# 19_WIFI_BLE.net
KiCad netlist of a schematic drawn in Altium Designer
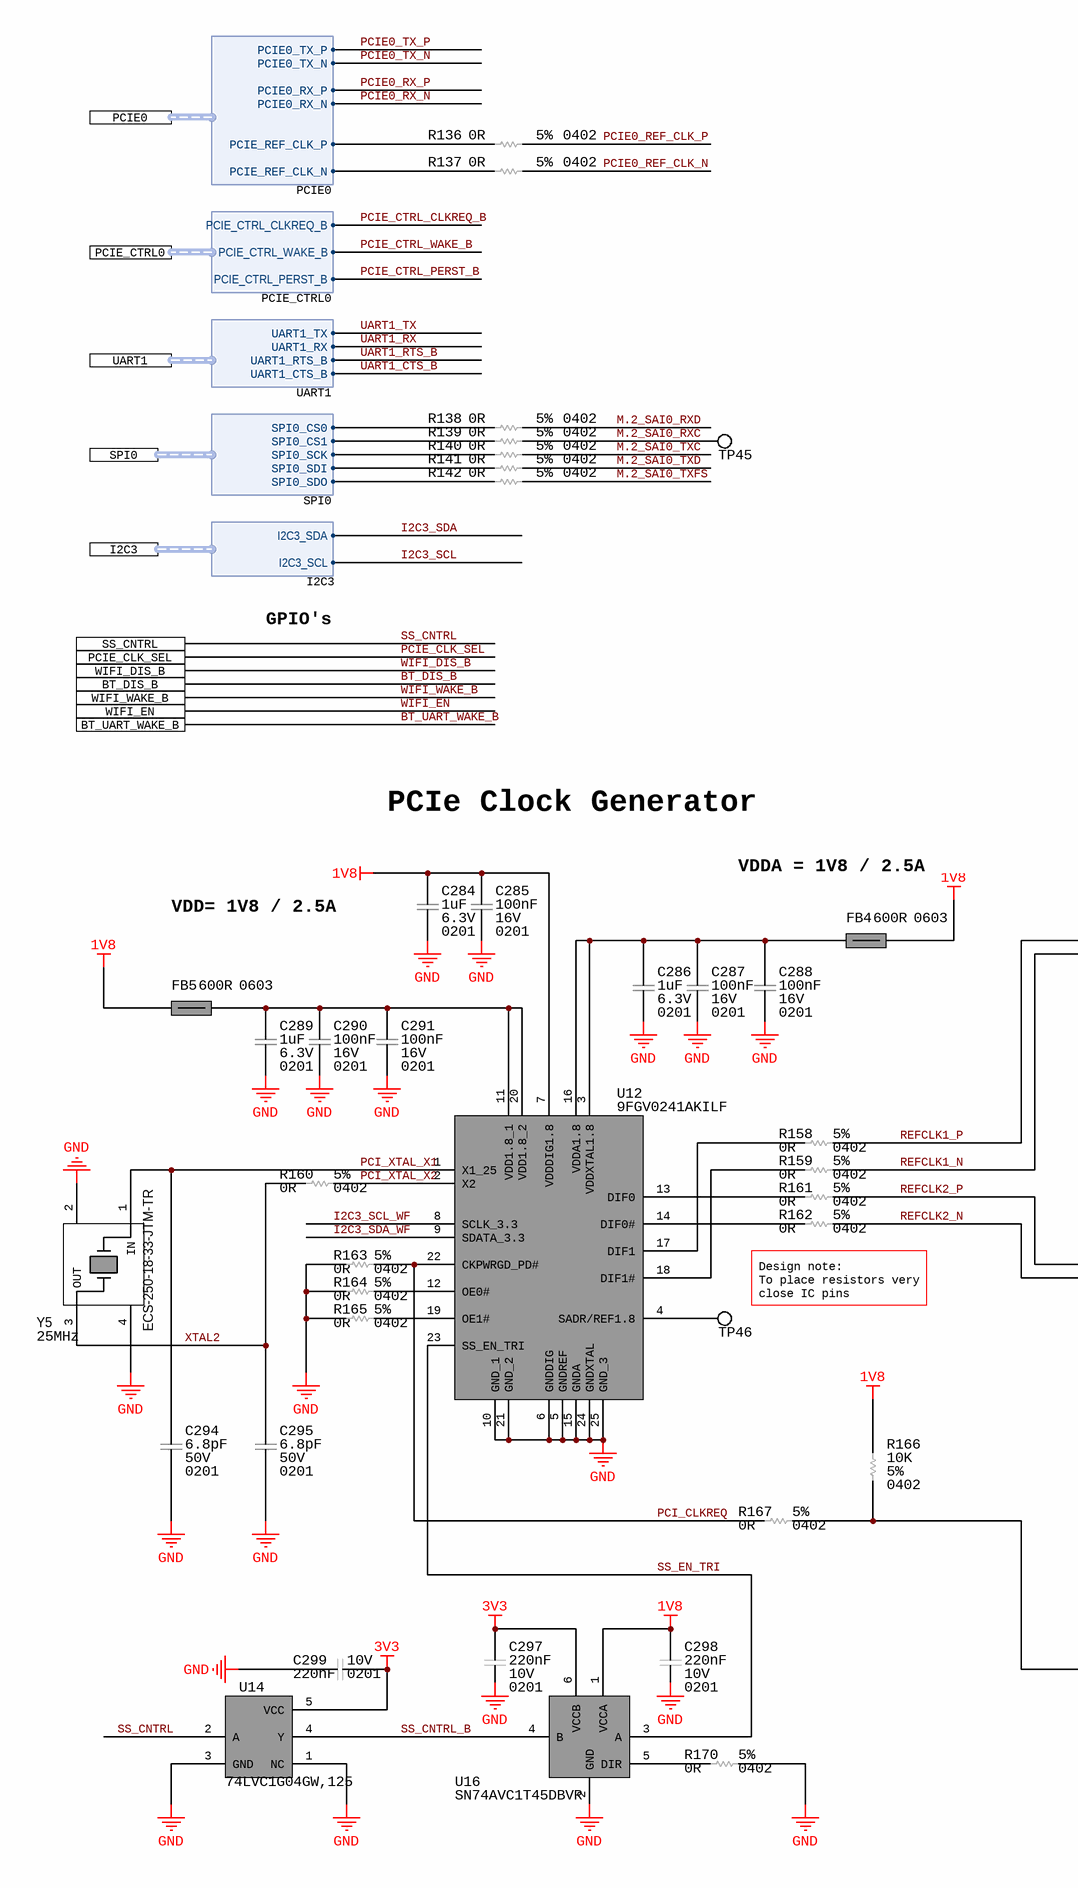
[diagram p0: 19_WIFI_BLE.SchDoc, left]
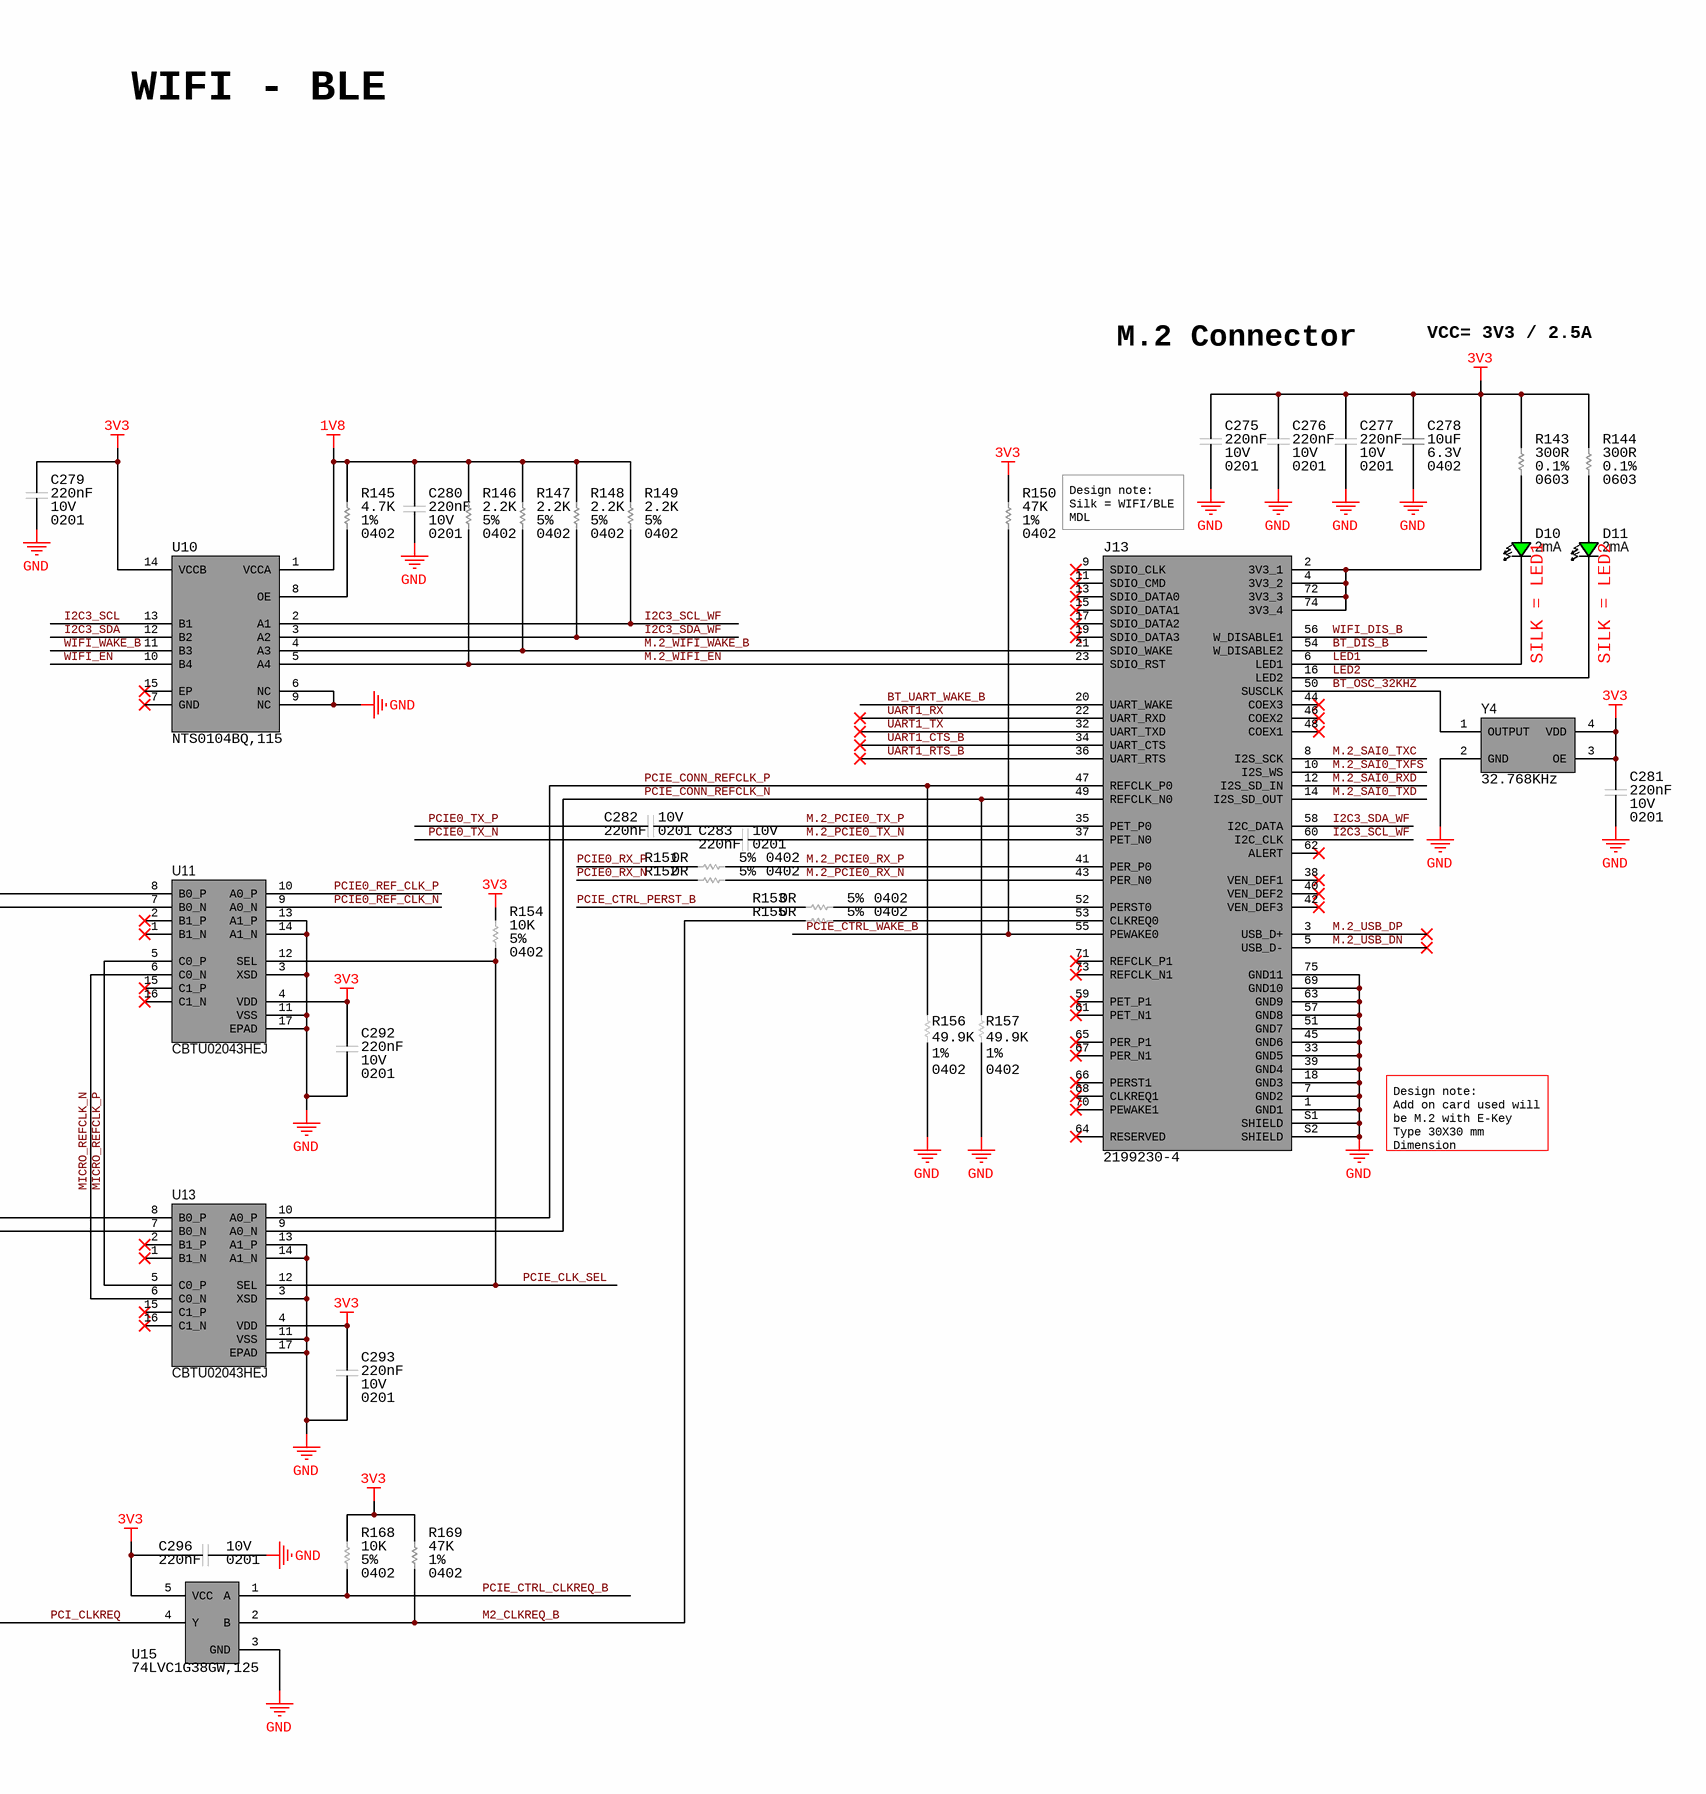
[diagram p1: 19_WIFI_BLE.SchDoc, right]

(export (version "E")
  (design (tool "Eeschema 10.0.6"))
  (components
    (comp (ref "C275")
      (value "LMK063BJ224MP-F")
      (footprint "CAP_0201_CAPC0603X03N")
      (description "Multilayer Ceramic Capacitors (High dielectric type), 10V, 0.22 uF, ± 20 %, 0201, X5R, RoHS")
      (fields
        (field (name "MANUFACTURER") "Taiyo Yuden")
        (field (name "TOLERANCE") "20%")
        (field (name "VOLTAGE RATING (DC)") "10V")
        (field (name "CAPACITANCE") "220nF")
        (field (name "CASE/PACKAGE") "0201")
      )
      (libsource (lib "Electronic Devices_LIB") (part "CAP_0.22UF_10V_X5R_0201"))
    )
    (comp (ref "C276")
      (value "LMK063BJ224MP-F")
      (footprint "CAP_0201_CAPC0603X03N")
      (description "Multilayer Ceramic Capacitors (High dielectric type), 10V, 0.22 uF, ± 20 %, 0201, X5R, RoHS")
      (fields
        (field (name "MANUFACTURER") "Taiyo Yuden")
        (field (name "TOLERANCE") "20%")
        (field (name "VOLTAGE RATING (DC)") "10V")
        (field (name "CAPACITANCE") "220nF")
        (field (name "CASE/PACKAGE") "0201")
      )
      (libsource (lib "Electronic Devices_LIB") (part "CAP_0.22UF_10V_X5R_0201"))
    )
    (comp (ref "C277")
      (value "LMK063BJ224MP-F")
      (footprint "CAP_0201_CAPC0603X03N")
      (description "Multilayer Ceramic Capacitors (High dielectric type), 10V, 0.22 uF, ± 20 %, 0201, X5R, RoHS")
      (fields
        (field (name "MANUFACTURER") "Taiyo Yuden")
        (field (name "TOLERANCE") "20%")
        (field (name "VOLTAGE RATING (DC)") "10V")
        (field (name "CAPACITANCE") "220nF")
        (field (name "CASE/PACKAGE") "0201")
      )
      (libsource (lib "Electronic Devices_LIB") (part "CAP_0.22UF_10V_X5R_0201"))
    )
    (comp (ref "C278")
      (value "CL05A106MQ5NUNC")
      (footprint "CAP_0402_CAPC1005X05N")
      (description "Cap Ceramic 10uF 6.3V X5R 20% SMD 0402 85C T/R")
      (fields
        (field (name "MANUFACTURER") "Samsung")
        (field (name "TOLERANCE") "20%")
        (field (name "CASE/PACKAGE") "0402")
        (field (name "CAPACITANCE") "10uF")
        (field (name "VOLTAGE RATING") "6.3V")
      )
      (libsource (lib "Electronic Devices_LIB") (part "CAP_10UF_6.3V_X5R_0402"))
    )
    (comp (ref "C279")
      (value "LMK063BJ224MP-F")
      (footprint "CAP_0201_CAPC0603X03N")
      (description "Multilayer Ceramic Capacitors (High dielectric type), 10V, 0.22 uF, ± 20 %, 0201, X5R, RoHS")
      (fields
        (field (name "MANUFACTURER") "Taiyo Yuden")
        (field (name "TOLERANCE") "20%")
        (field (name "VOLTAGE RATING (DC)") "10V")
        (field (name "CAPACITANCE") "220nF")
        (field (name "CASE/PACKAGE") "0201")
      )
      (libsource (lib "Electronic Devices_LIB") (part "CAP_0.22UF_10V_X5R_0201"))
    )
    (comp (ref "C280")
      (value "LMK063BJ224MP-F")
      (footprint "CAP_0201_CAPC0603X03N")
      (description "Multilayer Ceramic Capacitors (High dielectric type), 10V, 0.22 uF, ± 20 %, 0201, X5R, RoHS")
      (fields
        (field (name "MANUFACTURER") "Taiyo Yuden")
        (field (name "TOLERANCE") "20%")
        (field (name "VOLTAGE RATING (DC)") "10V")
        (field (name "CAPACITANCE") "220nF")
        (field (name "CASE/PACKAGE") "0201")
      )
      (libsource (lib "Electronic Devices_LIB") (part "CAP_0.22UF_10V_X5R_0201"))
    )
    (comp (ref "C281")
      (value "LMK063BJ224MP-F")
      (footprint "CAP_0201_CAPC0603X03N")
      (description "Multilayer Ceramic Capacitors (High dielectric type), 10V, 0.22 uF, ± 20 %, 0201, X5R, RoHS")
      (fields
        (field (name "MANUFACTURER") "Taiyo Yuden")
        (field (name "TOLERANCE") "20%")
        (field (name "VOLTAGE RATING (DC)") "10V")
        (field (name "CAPACITANCE") "220nF")
        (field (name "CASE/PACKAGE") "0201")
      )
      (libsource (lib "Electronic Devices_LIB") (part "CAP_0.22UF_10V_X5R_0201"))
    )
    (comp (ref "C282")
      (value "LMK063BJ224MP-F")
      (footprint "CAP_0201_CAPC0603X03N")
      (description "Multilayer Ceramic Capacitors (High dielectric type), 10V, 0.22 uF, ± 20 %, 0201, X5R, RoHS")
      (fields
        (field (name "MANUFACTURER") "Taiyo Yuden")
        (field (name "TOLERANCE") "20%")
        (field (name "VOLTAGE RATING (DC)") "10V")
        (field (name "CAPACITANCE") "220nF")
        (field (name "CASE/PACKAGE") "0201")
      )
      (libsource (lib "Electronic Devices_LIB") (part "CAP_0.22UF_10V_X5R_0201"))
    )
    (comp (ref "C283")
      (value "LMK063BJ224MP-F")
      (footprint "CAP_0201_CAPC0603X03N")
      (description "Multilayer Ceramic Capacitors (High dielectric type), 10V, 0.22 uF, ± 20 %, 0201, X5R, RoHS")
      (fields
        (field (name "MANUFACTURER") "Taiyo Yuden")
        (field (name "TOLERANCE") "20%")
        (field (name "VOLTAGE RATING (DC)") "10V")
        (field (name "CAPACITANCE") "220nF")
        (field (name "CASE/PACKAGE") "0201")
      )
      (libsource (lib "Electronic Devices_LIB") (part "CAP_0.22UF_10V_X5R_0201"))
    )
    (comp (ref "C284")
      (value "02016D105MAT2A")
      (footprint "CAP_0201_CAPC0603X03N")
      (description "0201 1 uF 6.3 V ±20 % Tolerance X5R Surface Mount Multilayer Ceramic Capacitor")
      (fields
        (field (name "MANUFACTURER") "Kyocera AVX")
        (field (name "TOLERANCE") "20%")
        (field (name "VOLTAGE RATING (DC)") "6.3V")
        (field (name "CAPACITANCE") "1uF")
        (field (name "CASE/PACKAGE") "0201")
      )
      (libsource (lib "Electronic Devices_LIB") (part "CAP_1UF_6.3V_X5R_0201"))
    )
    (comp (ref "C285")
      (value "GRM033C71C104KE14D")
      (footprint "CAP_0201_CAPC0603X03N")
      (description "Multilayer Ceramic Capacitor, 0.1 uF, 16 V, ± 10%, X7S, 0201 [0603 Metric]")
      (fields
        (field (name "MANUFACTURER") "Murata")
        (field (name "TOLERANCE") "10%")
        (field (name "VOLTAGE RATING") "16V")
        (field (name "CAPACITANCE") "100nF")
        (field (name "CASE/PACKAGE") "0201")
      )
      (libsource (lib "Electronic Devices_LIB") (part "CAP_100nF_16V_X7S_0201"))
    )
    (comp (ref "C286")
      (value "02016D105MAT2A")
      (footprint "CAP_0201_CAPC0603X03N")
      (description "0201 1 uF 6.3 V ±20 % Tolerance X5R Surface Mount Multilayer Ceramic Capacitor")
      (fields
        (field (name "MANUFACTURER") "Kyocera AVX")
        (field (name "TOLERANCE") "20%")
        (field (name "VOLTAGE RATING (DC)") "6.3V")
        (field (name "CAPACITANCE") "1uF")
        (field (name "CASE/PACKAGE") "0201")
      )
      (libsource (lib "Electronic Devices_LIB") (part "CAP_1UF_6.3V_X5R_0201"))
    )
    (comp (ref "C287")
      (value "GRM033C71C104KE14D")
      (footprint "CAP_0201_CAPC0603X03N")
      (description "Multilayer Ceramic Capacitor, 0.1 uF, 16 V, ± 10%, X7S, 0201 [0603 Metric]")
      (fields
        (field (name "MANUFACTURER") "Murata")
        (field (name "TOLERANCE") "10%")
        (field (name "VOLTAGE RATING") "16V")
        (field (name "CAPACITANCE") "100nF")
        (field (name "CASE/PACKAGE") "0201")
      )
      (libsource (lib "Electronic Devices_LIB") (part "CAP_100nF_16V_X7S_0201"))
    )
    (comp (ref "C288")
      (value "GRM033C71C104KE14D")
      (footprint "CAP_0201_CAPC0603X03N")
      (description "Multilayer Ceramic Capacitor, 0.1 uF, 16 V, ± 10%, X7S, 0201 [0603 Metric]")
      (fields
        (field (name "MANUFACTURER") "Murata")
        (field (name "TOLERANCE") "10%")
        (field (name "VOLTAGE RATING") "16V")
        (field (name "CAPACITANCE") "100nF")
        (field (name "CASE/PACKAGE") "0201")
      )
      (libsource (lib "Electronic Devices_LIB") (part "CAP_100nF_16V_X7S_0201"))
    )
    (comp (ref "C289")
      (value "02016D105MAT2A")
      (footprint "CAP_0201_CAPC0603X03N")
      (description "0201 1 uF 6.3 V ±20 % Tolerance X5R Surface Mount Multilayer Ceramic Capacitor")
      (fields
        (field (name "MANUFACTURER") "Kyocera AVX")
        (field (name "TOLERANCE") "20%")
        (field (name "VOLTAGE RATING (DC)") "6.3V")
        (field (name "CAPACITANCE") "1uF")
        (field (name "CASE/PACKAGE") "0201")
      )
      (libsource (lib "Electronic Devices_LIB") (part "CAP_1UF_6.3V_X5R_0201"))
    )
    (comp (ref "C290")
      (value "GRM033C71C104KE14D")
      (footprint "CAP_0201_CAPC0603X03N")
      (description "Multilayer Ceramic Capacitor, 0.1 uF, 16 V, ± 10%, X7S, 0201 [0603 Metric]")
      (fields
        (field (name "MANUFACTURER") "Murata")
        (field (name "TOLERANCE") "10%")
        (field (name "VOLTAGE RATING") "16V")
        (field (name "CAPACITANCE") "100nF")
        (field (name "CASE/PACKAGE") "0201")
      )
      (libsource (lib "Electronic Devices_LIB") (part "CAP_100nF_16V_X7S_0201"))
    )
    (comp (ref "C291")
      (value "GRM033C71C104KE14D")
      (footprint "CAP_0201_CAPC0603X03N")
      (description "Multilayer Ceramic Capacitor, 0.1 uF, 16 V, ± 10%, X7S, 0201 [0603 Metric]")
      (fields
        (field (name "MANUFACTURER") "Murata")
        (field (name "TOLERANCE") "10%")
        (field (name "VOLTAGE RATING") "16V")
        (field (name "CAPACITANCE") "100nF")
        (field (name "CASE/PACKAGE") "0201")
      )
      (libsource (lib "Electronic Devices_LIB") (part "CAP_100nF_16V_X7S_0201"))
    )
    (comp (ref "C292")
      (value "LMK063BJ224MP-F")
      (footprint "CAP_0201_CAPC0603X03N")
      (description "Multilayer Ceramic Capacitors (High dielectric type), 10V, 0.22 uF, ± 20 %, 0201, X5R, RoHS")
      (fields
        (field (name "MANUFACTURER") "Taiyo Yuden")
        (field (name "TOLERANCE") "20%")
        (field (name "VOLTAGE RATING (DC)") "10V")
        (field (name "CAPACITANCE") "220nF")
        (field (name "CASE/PACKAGE") "0201")
      )
      (libsource (lib "Electronic Devices_LIB") (part "CAP_0.22UF_10V_X5R_0201"))
    )
    (comp (ref "C293")
      (value "LMK063BJ224MP-F")
      (footprint "CAP_0201_CAPC0603X03N")
      (description "Multilayer Ceramic Capacitors (High dielectric type), 10V, 0.22 uF, ± 20 %, 0201, X5R, RoHS")
      (fields
        (field (name "MANUFACTURER") "Taiyo Yuden")
        (field (name "TOLERANCE") "20%")
        (field (name "VOLTAGE RATING (DC)") "10V")
        (field (name "CAPACITANCE") "220nF")
        (field (name "CASE/PACKAGE") "0201")
      )
      (libsource (lib "Electronic Devices_LIB") (part "CAP_0.22UF_10V_X5R_0201"))
    )
    (comp (ref "C294")
      (value "GRM0335C1H6R8BA01D")
      (footprint "CAP_0201_CAPC0603X03N")
      (description "Cap Ceramic 6.8pF 50V C0G 0.1pF Pad SMD 0201 125C T/R")
      (fields
        (field (name "MANUFACTURER") "Murata")
        (field (name "CAPACITANCE") "6.8pF")
        (field (name "VOLTAGE RATING") "50V")
        (field (name "CASE/PACKAGE") "0201")
      )
      (libsource (lib "Electronic Devices_LIB") (part "CAP_6.8pF_50V_NP0_0201"))
    )
    (comp (ref "C295")
      (value "GRM0335C1H6R8BA01D")
      (footprint "CAP_0201_CAPC0603X03N")
      (description "Cap Ceramic 6.8pF 50V C0G 0.1pF Pad SMD 0201 125C T/R")
      (fields
        (field (name "MANUFACTURER") "Murata")
        (field (name "CAPACITANCE") "6.8pF")
        (field (name "VOLTAGE RATING") "50V")
        (field (name "CASE/PACKAGE") "0201")
      )
      (libsource (lib "Electronic Devices_LIB") (part "CAP_6.8pF_50V_NP0_0201"))
    )
    (comp (ref "C296")
      (value "LMK063BJ224MP-F")
      (footprint "CAP_0201_CAPC0603X03N")
      (description "Multilayer Ceramic Capacitors (High dielectric type), 10V, 0.22 uF, ± 20 %, 0201, X5R, RoHS")
      (fields
        (field (name "MANUFACTURER") "Taiyo Yuden")
        (field (name "TOLERANCE") "20%")
        (field (name "VOLTAGE RATING (DC)") "10V")
        (field (name "CAPACITANCE") "220nF")
        (field (name "CASE/PACKAGE") "0201")
      )
      (libsource (lib "Electronic Devices_LIB") (part "CAP_0.22UF_10V_X5R_0201"))
    )
    (comp (ref "C297")
      (value "LMK063BJ224MP-F")
      (footprint "CAP_0201_CAPC0603X03N")
      (description "Multilayer Ceramic Capacitors (High dielectric type), 10V, 0.22 uF, ± 20 %, 0201, X5R, RoHS")
      (fields
        (field (name "MANUFACTURER") "Taiyo Yuden")
        (field (name "TOLERANCE") "20%")
        (field (name "VOLTAGE RATING (DC)") "10V")
        (field (name "CAPACITANCE") "220nF")
        (field (name "CASE/PACKAGE") "0201")
      )
      (libsource (lib "Electronic Devices_LIB") (part "CAP_0.22UF_10V_X5R_0201"))
    )
    (comp (ref "C298")
      (value "LMK063BJ224MP-F")
      (footprint "CAP_0201_CAPC0603X03N")
      (description "Multilayer Ceramic Capacitors (High dielectric type), 10V, 0.22 uF, ± 20 %, 0201, X5R, RoHS")
      (fields
        (field (name "MANUFACTURER") "Taiyo Yuden")
        (field (name "TOLERANCE") "20%")
        (field (name "VOLTAGE RATING (DC)") "10V")
        (field (name "CAPACITANCE") "220nF")
        (field (name "CASE/PACKAGE") "0201")
      )
      (libsource (lib "Electronic Devices_LIB") (part "CAP_0.22UF_10V_X5R_0201"))
    )
    (comp (ref "C299")
      (value "LMK063BJ224MP-F")
      (footprint "CAP_0201_CAPC0603X03N")
      (description "Multilayer Ceramic Capacitors (High dielectric type), 10V, 0.22 uF, ± 20 %, 0201, X5R, RoHS")
      (fields
        (field (name "MANUFACTURER") "Taiyo Yuden")
        (field (name "TOLERANCE") "20%")
        (field (name "VOLTAGE RATING (DC)") "10V")
        (field (name "CAPACITANCE") "220nF")
        (field (name "CASE/PACKAGE") "0201")
      )
      (libsource (lib "Electronic Devices_LIB") (part "CAP_0.22UF_10V_X5R_0201"))
    )
    (comp (ref "D10")
      (value "APDA3020LZGCK")
      (footprint "LED_GREEN_APDA3020LZGCK")
      (description "LED GREEN CLEAR 2SMD R/A  1500mcd")
      (fields (field (name "MANUFACTURER") "Kingbright") (field (name "TEST CURRENT") "2mA"))
      (libsource (lib "Electronic Devices_LIB") (part "LED_DIO_GREEN_2mA_APDA3020LZGCK"))
    )
    (comp (ref "D11")
      (value "APDA3020LZGCK")
      (footprint "LED_GREEN_APDA3020LZGCK")
      (description "LED GREEN CLEAR 2SMD R/A  1500mcd")
      (fields (field (name "MANUFACTURER") "Kingbright") (field (name "TEST CURRENT") "2mA"))
      (libsource (lib "Electronic Devices_LIB") (part "LED_DIO_GREEN_2mA_APDA3020LZGCK"))
    )
    (comp (ref "FB4")
      (value "742792653")
      (footprint "IND_0603_INDC1608X08N")
      (description "Chip NTC Thermistors (Sensor), Resistance (at 25°C)=10kΩ, Resistance Tolerance (at 25°C)=±1%")
      (fields
        (field (name "MANUFACTURER") "Wurth Electronics")
        (field (name "TOLERANCE") "25%")
        (field (name "IMPEDANCE") "600R")
        (field (name "CASE CODE (IMPERIAL)") "0603")
      )
      (libsource (lib "Electronic Devices_LIB") (part "IND_FERRITE_BEADS_600R_300mA_0603_742792653"))
    )
    (comp (ref "FB5")
      (value "742792653")
      (footprint "IND_0603_INDC1608X08N")
      (description "Chip NTC Thermistors (Sensor), Resistance (at 25°C)=10kΩ, Resistance Tolerance (at 25°C)=±1%")
      (fields
        (field (name "MANUFACTURER") "Wurth Electronics")
        (field (name "TOLERANCE") "25%")
        (field (name "IMPEDANCE") "600R")
        (field (name "CASE CODE (IMPERIAL)") "0603")
      )
      (libsource (lib "Electronic Devices_LIB") (part "IND_FERRITE_BEADS_600R_300mA_0603_742792653"))
    )
    (comp (ref "J13")
      (value "2199230-4")
      (footprint "TE_21992304")
      (description "CONNECTOR, BACKPLANE, HOUSING, RCPT, 67POS, 2ROW; Connector Type: Card Edge; Seri")
      (fields (field (name "MANUFACTURER") "TE Connectivity"))
      (libsource (lib "Electronic Devices_LIB") (part "CONN_M.2_FEMALE_2199230-4"))
    )
    (comp (ref "R136")
      (value "ERJ-2GE0R00X")
      (footprint "RES_0402_RESC1005X04N")
      (description "SMD Chip Resistor, Jumper, 0 ohm, 100 mW, 0402 [1005 Metric], Thick Film, General Purpose")
      (fields
        (field (name "MANUFACTURER") "Panasonic")
        (field (name "CASE CODE (IMPERIAL)") "0402")
        (field (name "TOLERANCE") "5%")
        (field (name "RESISTANCE") "0R")
      )
      (libsource (lib "Electronic Devices_LIB") (part "RES_0R_5%_100mW_0402"))
    )
    (comp (ref "R137")
      (value "ERJ-2GE0R00X")
      (footprint "RES_0402_RESC1005X04N")
      (description "SMD Chip Resistor, Jumper, 0 ohm, 100 mW, 0402 [1005 Metric], Thick Film, General Purpose")
      (fields
        (field (name "MANUFACTURER") "Panasonic")
        (field (name "CASE CODE (IMPERIAL)") "0402")
        (field (name "TOLERANCE") "5%")
        (field (name "RESISTANCE") "0R")
      )
      (libsource (lib "Electronic Devices_LIB") (part "RES_0R_5%_100mW_0402"))
    )
    (comp (ref "R138")
      (value "ERJ-2GE0R00X")
      (footprint "RES_0402_RESC1005X04N")
      (description "SMD Chip Resistor, Jumper, 0 ohm, 100 mW, 0402 [1005 Metric], Thick Film, General Purpose")
      (fields
        (field (name "MANUFACTURER") "Panasonic")
        (field (name "CASE CODE (IMPERIAL)") "0402")
        (field (name "TOLERANCE") "5%")
        (field (name "RESISTANCE") "0R")
      )
      (libsource (lib "Electronic Devices_LIB") (part "RES_0R_5%_100mW_0402"))
    )
    (comp (ref "R139")
      (value "ERJ-2GE0R00X")
      (footprint "RES_0402_RESC1005X04N")
      (description "SMD Chip Resistor, Jumper, 0 ohm, 100 mW, 0402 [1005 Metric], Thick Film, General Purpose")
      (fields
        (field (name "MANUFACTURER") "Panasonic")
        (field (name "CASE CODE (IMPERIAL)") "0402")
        (field (name "TOLERANCE") "5%")
        (field (name "RESISTANCE") "0R")
      )
      (libsource (lib "Electronic Devices_LIB") (part "RES_0R_5%_100mW_0402"))
    )
    (comp (ref "R140")
      (value "ERJ-2GE0R00X")
      (footprint "RES_0402_RESC1005X04N")
      (description "SMD Chip Resistor, Jumper, 0 ohm, 100 mW, 0402 [1005 Metric], Thick Film, General Purpose")
      (fields
        (field (name "MANUFACTURER") "Panasonic")
        (field (name "CASE CODE (IMPERIAL)") "0402")
        (field (name "TOLERANCE") "5%")
        (field (name "RESISTANCE") "0R")
      )
      (libsource (lib "Electronic Devices_LIB") (part "RES_0R_5%_100mW_0402"))
    )
    (comp (ref "R141")
      (value "ERJ-2GE0R00X")
      (footprint "RES_0402_RESC1005X04N")
      (description "SMD Chip Resistor, Jumper, 0 ohm, 100 mW, 0402 [1005 Metric], Thick Film, General Purpose")
      (fields
        (field (name "MANUFACTURER") "Panasonic")
        (field (name "CASE CODE (IMPERIAL)") "0402")
        (field (name "TOLERANCE") "5%")
        (field (name "RESISTANCE") "0R")
      )
      (libsource (lib "Electronic Devices_LIB") (part "RES_0R_5%_100mW_0402"))
    )
    (comp (ref "R142")
      (value "ERJ-2GE0R00X")
      (footprint "RES_0402_RESC1005X04N")
      (description "SMD Chip Resistor, Jumper, 0 ohm, 100 mW, 0402 [1005 Metric], Thick Film, General Purpose")
      (fields
        (field (name "MANUFACTURER") "Panasonic")
        (field (name "CASE CODE (IMPERIAL)") "0402")
        (field (name "TOLERANCE") "5%")
        (field (name "RESISTANCE") "0R")
      )
      (libsource (lib "Electronic Devices_LIB") (part "RES_0R_5%_100mW_0402"))
    )
    (comp (ref "R143")
      (value "RT0603BRD07300RL")
      (footprint "RES_0603_RESC1608X04N")
      (description "Res Thin Film 0603 300 Ohm 0.1% 0.1W(1/10W) ±25ppm/C Pad SMD T/R")
      (fields
        (field (name "MANUFACTURER") "Yageo")
        (field (name "CASE CODE (IMPERIAL)") "0603")
        (field (name "TOLERANCE") "0.1%")
        (field (name "RESISTANCE") "300R")
      )
      (libsource (lib "Electronic Devices_LIB") (part "RES_300R_0.1%_100mW_0603"))
    )
    (comp (ref "R144")
      (value "RT0603BRD07300RL")
      (footprint "RES_0603_RESC1608X04N")
      (description "Res Thin Film 0603 300 Ohm 0.1% 0.1W(1/10W) ±25ppm/C Pad SMD T/R")
      (fields
        (field (name "MANUFACTURER") "Yageo")
        (field (name "CASE CODE (IMPERIAL)") "0603")
        (field (name "TOLERANCE") "0.1%")
        (field (name "RESISTANCE") "300R")
      )
      (libsource (lib "Electronic Devices_LIB") (part "RES_300R_0.1%_100mW_0603"))
    )
    (comp (ref "R145")
      (value "ERJ-2RKF4701X")
      (footprint "RES_0402_RESC1005X04N")
      (description "Res Thick Film 0402 4.7K Ohm 1% 0.1W ±100ppm/°C Molded SMD Punched Carrier T/R")
      (fields
        (field (name "MANUFACTURER") "Panasonic")
        (field (name "TOLERANCE") "1%")
        (field (name "CASE CODE (IMPERIAL)") "0402")
        (field (name "RESISTANCE") "4.7K")
      )
      (libsource (lib "Electronic Devices_LIB") (part "RES_4.7K_1%_100mW_0402"))
    )
    (comp (ref "R146")
      (value "RC0402JR-072K2L")
      (footprint "RES_0402_RESC1005X04N")
      (description "SMD Chip Resistor, 2.2 kOhm, ± 5%, 63 mW, 0402 [1005 Metric], Thick Film, General Purpose")
      (fields
        (field (name "MANUFACTURER") "Yageo")
        (field (name "TOLERANCE") "5%")
        (field (name "RESISTANCE") "2.2K")
        (field (name "CASE/PACKAGE") "0402")
      )
      (libsource (lib "Electronic Devices_LIB") (part "RES_2.2K_5%_63mW_0402"))
    )
    (comp (ref "R147")
      (value "RC0402JR-072K2L")
      (footprint "RES_0402_RESC1005X04N")
      (description "SMD Chip Resistor, 2.2 kOhm, ± 5%, 63 mW, 0402 [1005 Metric], Thick Film, General Purpose")
      (fields
        (field (name "MANUFACTURER") "Yageo")
        (field (name "TOLERANCE") "5%")
        (field (name "RESISTANCE") "2.2K")
        (field (name "CASE/PACKAGE") "0402")
      )
      (libsource (lib "Electronic Devices_LIB") (part "RES_2.2K_5%_63mW_0402"))
    )
    (comp (ref "R148")
      (value "RC0402JR-072K2L")
      (footprint "RES_0402_RESC1005X04N")
      (description "SMD Chip Resistor, 2.2 kOhm, ± 5%, 63 mW, 0402 [1005 Metric], Thick Film, General Purpose")
      (fields
        (field (name "MANUFACTURER") "Yageo")
        (field (name "TOLERANCE") "5%")
        (field (name "RESISTANCE") "2.2K")
        (field (name "CASE/PACKAGE") "0402")
      )
      (libsource (lib "Electronic Devices_LIB") (part "RES_2.2K_5%_63mW_0402"))
    )
    (comp (ref "R149")
      (value "RC0402JR-072K2L")
      (footprint "RES_0402_RESC1005X04N")
      (description "SMD Chip Resistor, 2.2 kOhm, ± 5%, 63 mW, 0402 [1005 Metric], Thick Film, General Purpose")
      (fields
        (field (name "MANUFACTURER") "Yageo")
        (field (name "TOLERANCE") "5%")
        (field (name "RESISTANCE") "2.2K")
        (field (name "CASE/PACKAGE") "0402")
      )
      (libsource (lib "Electronic Devices_LIB") (part "RES_2.2K_5%_63mW_0402"))
    )
    (comp (ref "R150")
      (value "ERJ-2RKF4702X")
      (footprint "RES_0402_RESC1005X04N")
      (description "Res Thick Film 0402 47K Ohm 1% 0.1W ±100ppm/°C Molded SMD Punched Carrier T/R")
      (fields
        (field (name "MANUFACTURER") "Panasonic")
        (field (name "TOLERANCE") "1%")
        (field (name "RESISTANCE") "47K")
        (field (name "CASE/PACKAGE") "0402")
      )
      (libsource (lib "Electronic Devices_LIB") (part "RES_47K_1%_100MW_0402"))
    )
    (comp (ref "R151")
      (value "ERJ-2GE0R00X")
      (footprint "RES_0402_RESC1005X04N")
      (description "SMD Chip Resistor, Jumper, 0 ohm, 100 mW, 0402 [1005 Metric], Thick Film, General Purpose")
      (fields
        (field (name "MANUFACTURER") "Panasonic")
        (field (name "CASE CODE (IMPERIAL)") "0402")
        (field (name "TOLERANCE") "5%")
        (field (name "RESISTANCE") "0R")
      )
      (libsource (lib "Electronic Devices_LIB") (part "RES_0R_5%_100mW_0402"))
    )
    (comp (ref "R152")
      (value "ERJ-2GE0R00X")
      (footprint "RES_0402_RESC1005X04N")
      (description "SMD Chip Resistor, Jumper, 0 ohm, 100 mW, 0402 [1005 Metric], Thick Film, General Purpose")
      (fields
        (field (name "MANUFACTURER") "Panasonic")
        (field (name "CASE CODE (IMPERIAL)") "0402")
        (field (name "TOLERANCE") "5%")
        (field (name "RESISTANCE") "0R")
      )
      (libsource (lib "Electronic Devices_LIB") (part "RES_0R_5%_100mW_0402"))
    )
    (comp (ref "R153")
      (value "ERJ-2GE0R00X")
      (footprint "RES_0402_RESC1005X04N")
      (description "SMD Chip Resistor, Jumper, 0 ohm, 100 mW, 0402 [1005 Metric], Thick Film, General Purpose")
      (fields
        (field (name "MANUFACTURER") "Panasonic")
        (field (name "CASE CODE (IMPERIAL)") "0402")
        (field (name "TOLERANCE") "5%")
        (field (name "RESISTANCE") "0R")
      )
      (libsource (lib "Electronic Devices_LIB") (part "RES_0R_5%_100mW_0402"))
    )
    (comp (ref "R154")
      (value "ERJ-2GEJ103X")
      (footprint "RES_0402_RESC1005X04N")
      (description "Res Thick Film 0402 10K Ohm 5% 1/10W ±200ppm/°C Molded SMD Punched Carrier T/R")
      (fields
        (field (name "MANUFACTURER") "Panasonic")
        (field (name "TOLERANCE") "5%")
        (field (name "RESISTANCE") "10K")
        (field (name "CASE/PACKAGE") "0402")
      )
      (libsource (lib "Electronic Devices_LIB") (part "RES_10K_5%_100mW_0402"))
    )
    (comp (ref "R155")
      (value "ERJ-2GE0R00X")
      (footprint "RES_0402_RESC1005X04N")
      (description "SMD Chip Resistor, Jumper, 0 ohm, 100 mW, 0402 [1005 Metric], Thick Film, General Purpose")
      (fields
        (field (name "MANUFACTURER") "Panasonic")
        (field (name "CASE CODE (IMPERIAL)") "0402")
        (field (name "TOLERANCE") "5%")
        (field (name "RESISTANCE") "0R")
      )
      (libsource (lib "Electronic Devices_LIB") (part "RES_0R_5%_100mW_0402"))
    )
    (comp (ref "R156")
      (value "CRCW040249K9FKED")
      (footprint "RES_0402_RESC1005X04N")
      (description "Res Thick Film 0402 49.9K Ohm 1% 1/16W ±100ppm/°C Molded SMD SMD Paper T/R")
      (fields
        (field (name "MANUFACTURER") "Vishay")
        (field (name "RESISTANCE") "49.9K")
        (field (name "TOLERANCE") "1%")
        (field (name "CASE/PACKAGE") "0402")
      )
      (libsource (lib "Electronic Devices_LIB") (part "RES_49.9K_1%_0.0625W_0402"))
    )
    (comp (ref "R157")
      (value "CRCW040249K9FKED")
      (footprint "RES_0402_RESC1005X04N")
      (description "Res Thick Film 0402 49.9K Ohm 1% 1/16W ±100ppm/°C Molded SMD SMD Paper T/R")
      (fields
        (field (name "MANUFACTURER") "Vishay")
        (field (name "RESISTANCE") "49.9K")
        (field (name "TOLERANCE") "1%")
        (field (name "CASE/PACKAGE") "0402")
      )
      (libsource (lib "Electronic Devices_LIB") (part "RES_49.9K_1%_0.0625W_0402"))
    )
    (comp (ref "R158")
      (value "ERJ-2GE0R00X")
      (footprint "RES_0402_RESC1005X04N")
      (description "SMD Chip Resistor, Jumper, 0 ohm, 100 mW, 0402 [1005 Metric], Thick Film, General Purpose")
      (fields
        (field (name "MANUFACTURER") "Panasonic")
        (field (name "CASE CODE (IMPERIAL)") "0402")
        (field (name "TOLERANCE") "5%")
        (field (name "RESISTANCE") "0R")
      )
      (libsource (lib "Electronic Devices_LIB") (part "RES_0R_5%_100mW_0402"))
    )
    (comp (ref "R159")
      (value "ERJ-2GE0R00X")
      (footprint "RES_0402_RESC1005X04N")
      (description "SMD Chip Resistor, Jumper, 0 ohm, 100 mW, 0402 [1005 Metric], Thick Film, General Purpose")
      (fields
        (field (name "MANUFACTURER") "Panasonic")
        (field (name "CASE CODE (IMPERIAL)") "0402")
        (field (name "TOLERANCE") "5%")
        (field (name "RESISTANCE") "0R")
      )
      (libsource (lib "Electronic Devices_LIB") (part "RES_0R_5%_100mW_0402"))
    )
    (comp (ref "R160")
      (value "ERJ-2GE0R00X")
      (footprint "RES_0402_RESC1005X04N")
      (description "SMD Chip Resistor, Jumper, 0 ohm, 100 mW, 0402 [1005 Metric], Thick Film, General Purpose")
      (fields
        (field (name "MANUFACTURER") "Panasonic")
        (field (name "CASE CODE (IMPERIAL)") "0402")
        (field (name "TOLERANCE") "5%")
        (field (name "RESISTANCE") "0R")
      )
      (libsource (lib "Electronic Devices_LIB") (part "RES_0R_5%_100mW_0402"))
    )
    (comp (ref "R161")
      (value "ERJ-2GE0R00X")
      (footprint "RES_0402_RESC1005X04N")
      (description "SMD Chip Resistor, Jumper, 0 ohm, 100 mW, 0402 [1005 Metric], Thick Film, General Purpose")
      (fields
        (field (name "MANUFACTURER") "Panasonic")
        (field (name "CASE CODE (IMPERIAL)") "0402")
        (field (name "TOLERANCE") "5%")
        (field (name "RESISTANCE") "0R")
      )
      (libsource (lib "Electronic Devices_LIB") (part "RES_0R_5%_100mW_0402"))
    )
    (comp (ref "R162")
      (value "ERJ-2GE0R00X")
      (footprint "RES_0402_RESC1005X04N")
      (description "SMD Chip Resistor, Jumper, 0 ohm, 100 mW, 0402 [1005 Metric], Thick Film, General Purpose")
      (fields
        (field (name "MANUFACTURER") "Panasonic")
        (field (name "CASE CODE (IMPERIAL)") "0402")
        (field (name "TOLERANCE") "5%")
        (field (name "RESISTANCE") "0R")
      )
      (libsource (lib "Electronic Devices_LIB") (part "RES_0R_5%_100mW_0402"))
    )
    (comp (ref "R163")
      (value "ERJ-2GE0R00X")
      (footprint "RES_0402_RESC1005X04N")
      (description "SMD Chip Resistor, Jumper, 0 ohm, 100 mW, 0402 [1005 Metric], Thick Film, General Purpose")
      (fields
        (field (name "MANUFACTURER") "Panasonic")
        (field (name "CASE CODE (IMPERIAL)") "0402")
        (field (name "TOLERANCE") "5%")
        (field (name "RESISTANCE") "0R")
      )
      (libsource (lib "Electronic Devices_LIB") (part "RES_0R_5%_100mW_0402"))
    )
    (comp (ref "R164")
      (value "ERJ-2GE0R00X")
      (footprint "RES_0402_RESC1005X04N")
      (description "SMD Chip Resistor, Jumper, 0 ohm, 100 mW, 0402 [1005 Metric], Thick Film, General Purpose")
      (fields
        (field (name "MANUFACTURER") "Panasonic")
        (field (name "CASE CODE (IMPERIAL)") "0402")
        (field (name "TOLERANCE") "5%")
        (field (name "RESISTANCE") "0R")
      )
      (libsource (lib "Electronic Devices_LIB") (part "RES_0R_5%_100mW_0402"))
    )
    (comp (ref "R165")
      (value "ERJ-2GE0R00X")
      (footprint "RES_0402_RESC1005X04N")
      (description "SMD Chip Resistor, Jumper, 0 ohm, 100 mW, 0402 [1005 Metric], Thick Film, General Purpose")
      (fields
        (field (name "MANUFACTURER") "Panasonic")
        (field (name "CASE CODE (IMPERIAL)") "0402")
        (field (name "TOLERANCE") "5%")
        (field (name "RESISTANCE") "0R")
      )
      (libsource (lib "Electronic Devices_LIB") (part "RES_0R_5%_100mW_0402"))
    )
    (comp (ref "R166")
      (value "ERJ-2GEJ103X")
      (footprint "RES_0402_RESC1005X04N")
      (description "Res Thick Film 0402 10K Ohm 5% 1/10W ±200ppm/°C Molded SMD Punched Carrier T/R")
      (fields
        (field (name "MANUFACTURER") "Panasonic")
        (field (name "TOLERANCE") "5%")
        (field (name "RESISTANCE") "10K")
        (field (name "CASE/PACKAGE") "0402")
      )
      (libsource (lib "Electronic Devices_LIB") (part "RES_10K_5%_100mW_0402"))
    )
    (comp (ref "R167")
      (value "ERJ-2GE0R00X")
      (footprint "RES_0402_RESC1005X04N")
      (description "SMD Chip Resistor, Jumper, 0 ohm, 100 mW, 0402 [1005 Metric], Thick Film, General Purpose")
      (fields
        (field (name "MANUFACTURER") "Panasonic")
        (field (name "CASE CODE (IMPERIAL)") "0402")
        (field (name "TOLERANCE") "5%")
        (field (name "RESISTANCE") "0R")
      )
      (libsource (lib "Electronic Devices_LIB") (part "RES_0R_5%_100mW_0402"))
    )
    (comp (ref "R168")
      (value "ERJ-2GEJ103X")
      (footprint "RES_0402_RESC1005X04N")
      (description "Res Thick Film 0402 10K Ohm 5% 1/10W ±200ppm/°C Molded SMD Punched Carrier T/R")
      (fields
        (field (name "MANUFACTURER") "Panasonic")
        (field (name "TOLERANCE") "5%")
        (field (name "RESISTANCE") "10K")
        (field (name "CASE/PACKAGE") "0402")
      )
      (libsource (lib "Electronic Devices_LIB") (part "RES_10K_5%_100mW_0402"))
    )
    (comp (ref "R169")
      (value "ERJ-2RKF4702X")
      (footprint "RES_0402_RESC1005X04N")
      (description "Res Thick Film 0402 47K Ohm 1% 0.1W ±100ppm/°C Molded SMD Punched Carrier T/R")
      (fields
        (field (name "MANUFACTURER") "Panasonic")
        (field (name "TOLERANCE") "1%")
        (field (name "RESISTANCE") "47K")
        (field (name "CASE/PACKAGE") "0402")
      )
      (libsource (lib "Electronic Devices_LIB") (part "RES_47K_1%_100MW_0402"))
    )
    (comp (ref "R170")
      (value "ERJ-2GE0R00X")
      (footprint "RES_0402_RESC1005X04N")
      (description "SMD Chip Resistor, Jumper, 0 ohm, 100 mW, 0402 [1005 Metric], Thick Film, General Purpose")
      (fields
        (field (name "MANUFACTURER") "Panasonic")
        (field (name "CASE CODE (IMPERIAL)") "0402")
        (field (name "TOLERANCE") "5%")
        (field (name "RESISTANCE") "0R")
      )
      (libsource (lib "Electronic Devices_LIB") (part "RES_0R_5%_100mW_0402"))
    )
    (comp (ref "TP45")
      (value "NO COMPONENT")
      (footprint "TP_PAD_0.5MM_SMD_ROUND")
      (description "Test Point, SMD pad, round, 1.5mm, 1.6mm, 3mm diameter")
      (libsource (lib "Electronic Devices_LIB") (part "TP_PAD_SMD_SMALL"))
    )
    (comp (ref "TP46")
      (value "NO COMPONENT")
      (footprint "TP_PAD_0.5MM_SMD_ROUND")
      (description "Test Point, SMD pad, round, 1.5mm, 1.6mm, 3mm diameter")
      (libsource (lib "Electronic Devices_LIB") (part "TP_PAD_SMD_SMALL"))
    )
    (comp (ref "U10")
      (value "NTS0104BQ,115")
      (footprint "QFN50P300X250X100-15N")
      (description "Voltage Level Translator Bidirectional 1 Circuit 4 Channel 50Mbps 14-DHVQFN (2.5x3)")
      (fields (field (name "MANUFACTURER") "NXP Semiconductors"))
      (libsource (lib "Electronic Devices_LIB") (part "IC_LEVEL_TRASLATE_4CH_NTS0104BQ,115"))
    )
    (comp (ref "U11")
      (value "CBTU02043HEJ")
      (footprint "IC_SW_TYPEC_CBTU02044HEJ")
      (description "USB 3.1 Gen 1 Type C switch / TAPE + REEL REEL 13\" Q1 NDP RoHS Compliant: Yes")
      (fields (field (name "MANUFACTURER") "NXP Semiconductors"))
      (libsource (lib "Electronic Devices_LIB") (part "IC_SWITCH_TYPEC_CBTU02043HEJ"))
    )
    (comp (ref "U12")
      (value "9FGV0241AKILF")
      (footprint "QFN50P400X400X100-25N-D")
      (description "Dual Output 1.8 V Very Low Power PCIE GEN1/2/3 Clock Generator - VFQFPN-24")
      (fields (field (name "MANUFACTURER") "Renesas"))
      (libsource (lib "Electronic Devices_LIB") (part "IC_CLOCK_PCIE_100MHZ_9FGV0241AKILF"))
    )
    (comp (ref "U13")
      (value "CBTU02043HEJ")
      (footprint "IC_SW_TYPEC_CBTU02044HEJ")
      (description "USB 3.1 Gen 1 Type C switch / TAPE + REEL REEL 13\" Q1 NDP RoHS Compliant: Yes")
      (fields (field (name "MANUFACTURER") "NXP Semiconductors"))
      (libsource (lib "Electronic Devices_LIB") (part "IC_SWITCH_TYPEC_CBTU02043HEJ"))
    )
    (comp (ref "U14")
      (value "74LVC1G04GW,125")
      (footprint "SOT65P210X110-5N")
      (description "74LVC Series 5.5 V Surface Mount Single Inverting Buffer - TSSOP-5")
      (fields (field (name "MANUFACTURER") "Nexperia"))
      (libsource (lib "Electronic Devices_LIB") (part "IC_INVERTER_1CH_74LVC1G04GW,125"))
    )
    (comp (ref "U15")
      (value "74LVC1G38GW,125")
      (footprint "SOT65P212X110-5N")
      (description "IC GATE NAND 1CH 2-INP 5-TSSOP")
      (fields (field (name "MANUFACTURER") "Nexperia"))
      (libsource (lib "Electronic Devices_LIB") (part "IC_GATE_NAND_1CH_74LVC1G38GW,125"))
    )
    (comp (ref "U16")
      (value "SN74AVC1T45DBVR")
      (footprint "SOT95P280X145-6N")
      (description "1.2V~3.6V 1 1 1.2V~3.6V 500Mbps SOT-23-6 Translators / Level Shifters ROHS")
      (fields (field (name "MANUFACTURER") "Texas Instruments"))
      (libsource (lib "Electronic Devices_LIB") (part "IC_LEVEL_TRANSLATOR_SN74AVC1T45DBVR"))
    )
    (comp (ref "Y4")
      (value "ASH7KW-32.768kHz-L-T")
      (footprint "CRYSTAL_32.768KHZ_ASH7KW32768kHzLT")
      (description "OSC XO 32.768KHZ CMOS SMD")
      (fields (field (name "MANUFACTURER") "Abracon") (field (name "FREQUENCY") "32.768KHz"))
      (libsource (lib "Electronic Devices_LIB") (part "CRYSTAL_ABRACON_32.768KHZ"))
    )
    (comp (ref "Y5")
      (value "ECS-250-18-33-JTM-TR")
      (footprint "CRYSTAL_ECS-250-18-33-JTM-TR")
      (description "Crystal 25MHz ±20ppm (Tol) ±20ppm (Stability) 18pF FUND 40Ohm 4-Pin Mini-CSMD T/R")
      (fields (field (name "MANUFACTURER") "ECS International") (field (name "FREQUENCY") "25MHz"))
      (libsource (lib "Electronic Devices_LIB") (part "CRYSTAL_ECS_25MHZ_ECS-250-18-33-JTM-TR"))
    )
  )
  (nets
    (net (code "6") (name "/BT_DIS_B") (class "Default")
      (node (ref "J13") (pin "54") (pinfunction "W_DISABLE2_54") (pintype "passive"))
    )
    (net (code "7") (name "/BT_OSC_32KHZ") (class "Default")
      (node (ref "J13") (pin "50") (pinfunction "SUSCLK_50") (pintype "passive"))
      (node (ref "Y4") (pin "1") (pinfunction "OUTPUT_1") (pintype "passive"))
    )
    (net (code "8") (name "/BT_UART_WAKE_B") (class "Default")
      (node (ref "J13") (pin "20") (pinfunction "UART_WAKE_20") (pintype "passive"))
    )
    (net (code "9") (name "/I2C3_SCL") (class "Default")
      (node (ref "U10") (pin "13") (pinfunction "B1_13") (pintype "passive"))
    )
    (net (code "10") (name "/I2C3_SCL_WF") (class "Default")
      (node (ref "J13") (pin "60") (pinfunction "I2C_CLK_60") (pintype "passive"))
      (node (ref "R149") (pin "1") (pinfunction "1_1") (pintype "passive"))
      (node (ref "U10") (pin "2") (pinfunction "A1_2") (pintype "passive"))
      (node (ref "U12") (pin "8") (pinfunction "SCLK_3.3_8") (pintype "passive"))
    )
    (net (code "11") (name "/I2C3_SDA") (class "Default")
      (node (ref "U10") (pin "12") (pinfunction "B2_12") (pintype "passive"))
    )
    (net (code "12") (name "/I2C3_SDA_WF") (class "Default")
      (node (ref "J13") (pin "58") (pinfunction "I2C_DATA_58") (pintype "passive"))
      (node (ref "R148") (pin "1") (pinfunction "1_1") (pintype "passive"))
      (node (ref "U10") (pin "3") (pinfunction "A2_3") (pintype "passive"))
      (node (ref "U12") (pin "9") (pinfunction "SDATA_3.3_9") (pintype "passive"))
    )
    (net (code "13") (name "/LED1") (class "Default")
      (node (ref "D10") (pin "1") (pinfunction "C_1") (pintype "passive"))
      (node (ref "J13") (pin "6") (pinfunction "LED1_6") (pintype "passive"))
    )
    (net (code "14") (name "/LED2") (class "Default")
      (node (ref "D11") (pin "1") (pinfunction "C_1") (pintype "passive"))
      (node (ref "J13") (pin "16") (pinfunction "LED2_16") (pintype "passive"))
    )
    (net (code "15") (name "/M.2_PCIE0_RX_N") (class "Default")
      (node (ref "J13") (pin "43") (pinfunction "PER_N0_43") (pintype "passive"))
      (node (ref "R152") (pin "2") (pinfunction "2_2") (pintype "passive"))
    )
    (net (code "16") (name "/M.2_PCIE0_RX_P") (class "Default")
      (node (ref "J13") (pin "41") (pinfunction "PER_P0_41") (pintype "passive"))
      (node (ref "R151") (pin "2") (pinfunction "2_2") (pintype "passive"))
    )
    (net (code "17") (name "/M.2_PCIE0_TX_N") (class "Default")
      (node (ref "C283") (pin "1") (pinfunction "1_1") (pintype "passive"))
      (node (ref "J13") (pin "37") (pinfunction "PET_N0_37") (pintype "passive"))
    )
    (net (code "18") (name "/M.2_PCIE0_TX_P") (class "Default")
      (node (ref "C282") (pin "1") (pinfunction "1_1") (pintype "passive"))
      (node (ref "J13") (pin "35") (pinfunction "PET_P0_35") (pintype "passive"))
    )
    (net (code "19") (name "/M.2_SAI0_RXC") (class "Default")
      (node (ref "R139") (pin "2") (pinfunction "2_2") (pintype "passive"))
      (node (ref "TP45") (pin "1") (pinfunction "1_1") (pintype "passive"))
    )
    (net (code "20") (name "/M.2_SAI0_RXD") (class "Default")
      (node (ref "J13") (pin "12") (pinfunction "I2S_SD_IN_12") (pintype "passive"))
      (node (ref "R138") (pin "2") (pinfunction "2_2") (pintype "passive"))
    )
    (net (code "21") (name "/M.2_SAI0_TXC") (class "Default")
      (node (ref "J13") (pin "8") (pinfunction "I2S_SCK_8") (pintype "passive"))
      (node (ref "R140") (pin "2") (pinfunction "2_2") (pintype "passive"))
    )
    (net (code "22") (name "/M.2_SAI0_TXD") (class "Default")
      (node (ref "J13") (pin "14") (pinfunction "I2S_SD_OUT_14") (pintype "passive"))
      (node (ref "R141") (pin "2") (pinfunction "2_2") (pintype "passive"))
    )
    (net (code "23") (name "/M.2_SAI0_TXFS") (class "Default")
      (node (ref "J13") (pin "10") (pinfunction "I2S_WS_10") (pintype "passive"))
      (node (ref "R142") (pin "2") (pinfunction "2_2") (pintype "passive"))
    )
    (net (code "24") (name "/M.2_USB_DN") (class "Default")
      (node (ref "J13") (pin "5") (pinfunction "USB_D-_5") (pintype "passive+no_connect"))
    )
    (net (code "25") (name "/M.2_USB_DP") (class "Default")
      (node (ref "J13") (pin "3") (pinfunction "USB_D+_3") (pintype "passive+no_connect"))
    )
    (net (code "26") (name "/M.2_WIFI_EN") (class "Default")
      (node (ref "J13") (pin "23") (pinfunction "SDIO_RST_23") (pintype "passive"))
      (node (ref "R146") (pin "1") (pinfunction "1_1") (pintype "passive"))
      (node (ref "U10") (pin "5") (pinfunction "A4_5") (pintype "passive"))
    )
    (net (code "27") (name "/M.2_WIFI_WAKE_B") (class "Default")
      (node (ref "J13") (pin "21") (pinfunction "SDIO_WAKE_21") (pintype "passive"))
      (node (ref "R147") (pin "1") (pinfunction "1_1") (pintype "passive"))
      (node (ref "U10") (pin "4") (pinfunction "A3_4") (pintype "passive"))
    )
    (net (code "28") (name "/M2_CLKREQ_B") (class "Default")
      (node (ref "R155") (pin "1") (pinfunction "1_1") (pintype "passive"))
      (node (ref "R169") (pin "1") (pinfunction "1_1") (pintype "passive"))
      (node (ref "U15") (pin "2") (pinfunction "B_2") (pintype "passive"))
    )
    (net (code "29") (name "/MICRO_REFCLK_N") (class "Default")
      (node (ref "U11") (pin "6") (pinfunction "C0_N_6") (pintype "passive"))
      (node (ref "U13") (pin "6") (pinfunction "C0_N_6") (pintype "passive"))
    )
    (net (code "30") (name "/MICRO_REFCLK_P") (class "Default")
      (node (ref "U11") (pin "5") (pinfunction "C0_P_5") (pintype "passive"))
      (node (ref "U13") (pin "5") (pinfunction "C0_P_5") (pintype "passive"))
    )
    (net (code "31") (name "/PCIE0_REF_CLK_N") (class "Default")
      (node (ref "R137") (pin "2") (pinfunction "2_2") (pintype "passive"))
      (node (ref "U11") (pin "9") (pinfunction "A0_N_9") (pintype "passive"))
    )
    (net (code "32") (name "/PCIE0_REF_CLK_P") (class "Default")
      (node (ref "R136") (pin "2") (pinfunction "2_2") (pintype "passive"))
      (node (ref "U11") (pin "10") (pinfunction "A0_P_10") (pintype "passive"))
    )
    (net (code "33") (name "/PCIE0_RX_N") (class "Default")
      (node (ref "R152") (pin "1") (pinfunction "1_1") (pintype "passive"))
    )
    (net (code "34") (name "/PCIE0_RX_P") (class "Default")
      (node (ref "R151") (pin "1") (pinfunction "1_1") (pintype "passive"))
    )
    (net (code "35") (name "/PCIE0_TX_N") (class "Default")
      (node (ref "C283") (pin "2") (pinfunction "2_2") (pintype "passive"))
    )
    (net (code "36") (name "/PCIE0_TX_P") (class "Default")
      (node (ref "C282") (pin "2") (pinfunction "2_2") (pintype "passive"))
    )
    (net (code "37") (name "/PCIE_CLK_SEL") (class "Default")
      (node (ref "R154") (pin "2") (pinfunction "2_2") (pintype "passive"))
      (node (ref "U11") (pin "12") (pinfunction "SEL_12") (pintype "passive"))
      (node (ref "U13") (pin "12") (pinfunction "SEL_12") (pintype "passive"))
    )
    (net (code "38") (name "/PCIE_CONN_REFCLK_N") (class "Default")
      (node (ref "J13") (pin "49") (pinfunction "REFCLK_N0_49") (pintype "passive"))
      (node (ref "R157") (pin "2") (pinfunction "2_2") (pintype "passive"))
      (node (ref "U13") (pin "9") (pinfunction "A0_N_9") (pintype "passive"))
    )
    (net (code "39") (name "/PCIE_CONN_REFCLK_P") (class "Default")
      (node (ref "J13") (pin "47") (pinfunction "REFCLK_P0_47") (pintype "passive"))
      (node (ref "R156") (pin "2") (pinfunction "2_2") (pintype "passive"))
      (node (ref "U13") (pin "10") (pinfunction "A0_P_10") (pintype "passive"))
    )
    (net (code "40") (name "/PCIE_CTRL_CLKREQ_B") (class "Default")
      (node (ref "R168") (pin "1") (pinfunction "1_1") (pintype "passive"))
      (node (ref "U15") (pin "1") (pinfunction "A_1") (pintype "passive"))
    )
    (net (code "41") (name "/PCIE_CTRL_PERST_B") (class "Default")
      (node (ref "R153") (pin "1") (pinfunction "1_1") (pintype "passive"))
    )
    (net (code "42") (name "/PCIE_CTRL_WAKE_B") (class "Default")
      (node (ref "J13") (pin "55") (pinfunction "PEWAKE0_55") (pintype "passive"))
      (node (ref "R150") (pin "1") (pinfunction "1_1") (pintype "passive"))
    )
    (net (code "43") (name "/PCIE_REF_CLK_N") (class "Default")
      (node (ref "R137") (pin "1") (pinfunction "1_1") (pintype "passive"))
    )
    (net (code "44") (name "/PCIE_REF_CLK_P") (class "Default")
      (node (ref "R136") (pin "1") (pinfunction "1_1") (pintype "passive"))
    )
    (net (code "45") (name "/PCI_CLKREQ") (class "Default")
      (node (ref "R163") (pin "2") (pinfunction "2_2") (pintype "passive"))
      (node (ref "R166") (pin "1") (pinfunction "1_1") (pintype "passive"))
      (node (ref "R167") (pin "1") (pinfunction "1_1") (pintype "passive"))
      (node (ref "R167") (pin "2") (pinfunction "2_2") (pintype "passive"))
      (node (ref "U12") (pin "22") (pinfunction "CKPWRGD_PD#_22") (pintype "passive"))
      (node (ref "U15") (pin "4") (pinfunction "Y_4") (pintype "passive"))
    )
    (net (code "46") (name "/PCI_XTAL_X1") (class "Default")
      (node (ref "C294") (pin "2") (pinfunction "2_2") (pintype "passive"))
      (node (ref "U12") (pin "1") (pinfunction "X1_25_1") (pintype "passive"))
      (node (ref "Y5") (pin "1") (pinfunction "IN_1") (pintype "passive"))
    )
    (net (code "47") (name "/PCI_XTAL_X2") (class "Default")
      (node (ref "R160") (pin "2") (pinfunction "2_2") (pintype "passive"))
      (node (ref "U12") (pin "2") (pinfunction "X2_2") (pintype "passive"))
    )
    (net (code "48") (name "/REFCLK1_N") (class "Default")
      (node (ref "R159") (pin "2") (pinfunction "2_2") (pintype "passive"))
      (node (ref "U11") (pin "7") (pinfunction "B0_N_7") (pintype "passive"))
    )
    (net (code "49") (name "/REFCLK1_P") (class "Default")
      (node (ref "R158") (pin "2") (pinfunction "2_2") (pintype "passive"))
      (node (ref "U11") (pin "8") (pinfunction "B0_P_8") (pintype "passive"))
    )
    (net (code "50") (name "/REFCLK2_N") (class "Default")
      (node (ref "R162") (pin "2") (pinfunction "2_2") (pintype "passive"))
      (node (ref "U13") (pin "7") (pinfunction "B0_N_7") (pintype "passive"))
    )
    (net (code "51") (name "/REFCLK2_P") (class "Default")
      (node (ref "R161") (pin "2") (pinfunction "2_2") (pintype "passive"))
      (node (ref "U13") (pin "8") (pinfunction "B0_P_8") (pintype "passive"))
    )
    (net (code "52") (name "/SPI0_CS0") (class "Default")
      (node (ref "R138") (pin "1") (pinfunction "1_1") (pintype "passive"))
    )
    (net (code "53") (name "/SPI0_CS1") (class "Default")
      (node (ref "R139") (pin "1") (pinfunction "1_1") (pintype "passive"))
    )
    (net (code "54") (name "/SPI0_SCK") (class "Default")
      (node (ref "R140") (pin "1") (pinfunction "1_1") (pintype "passive"))
    )
    (net (code "55") (name "/SPI0_SDI") (class "Default")
      (node (ref "R141") (pin "1") (pinfunction "1_1") (pintype "passive"))
    )
    (net (code "56") (name "/SPI0_SDO") (class "Default")
      (node (ref "R142") (pin "1") (pinfunction "1_1") (pintype "passive"))
    )
    (net (code "57") (name "/SS_CNTRL") (class "Default")
      (node (ref "U14") (pin "2") (pinfunction "A_2") (pintype "passive"))
    )
    (net (code "58") (name "/SS_CNTRL_B") (class "Default")
      (node (ref "U14") (pin "4") (pinfunction "Y_4") (pintype "passive"))
      (node (ref "U16") (pin "4") (pinfunction "B_4") (pintype "passive"))
    )
    (net (code "59") (name "/SS_EN_TRI") (class "Default")
      (node (ref "U12") (pin "23") (pinfunction "SS_EN_TRI_23") (pintype "passive"))
      (node (ref "U16") (pin "3") (pinfunction "A_3") (pintype "passive"))
    )
    (net (code "60") (name "/UART1_CTS_B") (class "Default")
      (node (ref "J13") (pin "34") (pinfunction "UART_CTS_34") (pintype "passive+no_connect"))
    )
    (net (code "61") (name "/UART1_RTS_B") (class "Default")
      (node (ref "J13") (pin "36") (pinfunction "UART_RTS_36") (pintype "passive+no_connect"))
    )
    (net (code "62") (name "/UART1_RX") (class "Default")
      (node (ref "J13") (pin "22") (pinfunction "UART_RXD_22") (pintype "passive+no_connect"))
    )
    (net (code "63") (name "/UART1_TX") (class "Default")
      (node (ref "J13") (pin "32") (pinfunction "UART_TXD_32") (pintype "passive+no_connect"))
    )
    (net (code "64") (name "/WIFI_DIS_B") (class "Default")
      (node (ref "J13") (pin "56") (pinfunction "W_DISABLE1_56") (pintype "passive"))
    )
    (net (code "65") (name "/WIFI_EN") (class "Default")
      (node (ref "U10") (pin "10") (pinfunction "B4_10") (pintype "passive"))
    )
    (net (code "66") (name "/WIFI_WAKE_B") (class "Default")
      (node (ref "U10") (pin "11") (pinfunction "B3_11") (pintype "passive"))
    )
    (net (code "67") (name "/XTAL2") (class "Default")
      (node (ref "C295") (pin "2") (pinfunction "2_2") (pintype "passive"))
      (node (ref "R160") (pin "1") (pinfunction "1_1") (pintype "passive"))
      (node (ref "Y5") (pin "3") (pinfunction "OUT_3") (pintype "passive"))
    )
    (net (code "73") (name "1V8") (class "Default")
      (node (ref "C280") (pin "2") (pinfunction "2_2") (pintype "passive"))
      (node (ref "C284") (pin "2") (pinfunction "2_2") (pintype "passive"))
      (node (ref "C285") (pin "2") (pinfunction "2_2") (pintype "passive"))
      (node (ref "C298") (pin "1") (pinfunction "1_1") (pintype "passive"))
      (node (ref "FB4") (pin "2") (pinfunction "2_2") (pintype "passive"))
      (node (ref "FB5") (pin "1") (pinfunction "1_1") (pintype "passive"))
      (node (ref "R145") (pin "2") (pinfunction "2_2") (pintype "passive"))
      (node (ref "R146") (pin "2") (pinfunction "2_2") (pintype "passive"))
      (node (ref "R147") (pin "2") (pinfunction "2_2") (pintype "passive"))
      (node (ref "R148") (pin "2") (pinfunction "2_2") (pintype "passive"))
      (node (ref "R149") (pin "2") (pinfunction "2_2") (pintype "passive"))
      (node (ref "R166") (pin "2") (pinfunction "2_2") (pintype "passive"))
      (node (ref "U10") (pin "1") (pinfunction "VCCA_1") (pintype "power_in"))
      (node (ref "U12") (pin "7") (pinfunction "VDDDIG1.8_7") (pintype "passive"))
      (node (ref "U16") (pin "1") (pinfunction "VCCA_1") (pintype "passive"))
    )
    (net (code "74") (name "3V3") (class "Default")
      (node (ref "C275") (pin "2") (pinfunction "2_2") (pintype "passive"))
      (node (ref "C276") (pin "2") (pinfunction "2_2") (pintype "passive"))
      (node (ref "C277") (pin "2") (pinfunction "2_2") (pintype "passive"))
      (node (ref "C278") (pin "2") (pinfunction "2_2") (pintype "passive"))
      (node (ref "C279") (pin "2") (pinfunction "2_2") (pintype "passive"))
      (node (ref "C281") (pin "2") (pinfunction "2_2") (pintype "passive"))
      (node (ref "C292") (pin "2") (pinfunction "2_2") (pintype "passive"))
      (node (ref "C293") (pin "2") (pinfunction "2_2") (pintype "passive"))
      (node (ref "C296") (pin "1") (pinfunction "1_1") (pintype "passive"))
      (node (ref "C297") (pin "1") (pinfunction "1_1") (pintype "passive"))
      (node (ref "C299") (pin "1") (pinfunction "1_1") (pintype "passive"))
      (node (ref "J13") (pin "2") (pinfunction "3V3_1_2") (pintype "passive"))
      (node (ref "J13") (pin "4") (pinfunction "3V3_2_4") (pintype "passive"))
      (node (ref "J13") (pin "72") (pinfunction "3V3_3_72") (pintype "passive"))
      (node (ref "J13") (pin "74") (pinfunction "3V3_4_74") (pintype "passive"))
      (node (ref "R143") (pin "2") (pinfunction "2_2") (pintype "passive"))
      (node (ref "R144") (pin "2") (pinfunction "2_2") (pintype "passive"))
      (node (ref "R150") (pin "2") (pinfunction "2_2") (pintype "passive"))
      (node (ref "R154") (pin "1") (pinfunction "1_1") (pintype "passive"))
      (node (ref "R168") (pin "2") (pinfunction "2_2") (pintype "passive"))
      (node (ref "R169") (pin "2") (pinfunction "2_2") (pintype "passive"))
      (node (ref "U10") (pin "14") (pinfunction "VCCB_14") (pintype "power_in"))
      (node (ref "U11") (pin "4") (pinfunction "VDD_4") (pintype "power_in"))
      (node (ref "U13") (pin "4") (pinfunction "VDD_4") (pintype "power_in"))
      (node (ref "U14") (pin "5") (pinfunction "VCC_5") (pintype "power_in"))
      (node (ref "U15") (pin "5") (pinfunction "VCC_5") (pintype "passive"))
      (node (ref "U16") (pin "6") (pinfunction "VCCB_6") (pintype "passive"))
      (node (ref "Y4") (pin "3") (pinfunction "OE_3") (pintype "passive"))
      (node (ref "Y4") (pin "4") (pinfunction "VDD_4") (pintype "passive"))
    )
    (net (code "75") (name "GND") (class "Default")
      (node (ref "C275") (pin "1") (pinfunction "1_1") (pintype "passive"))
      (node (ref "C276") (pin "1") (pinfunction "1_1") (pintype "passive"))
      (node (ref "C277") (pin "1") (pinfunction "1_1") (pintype "passive"))
      (node (ref "C278") (pin "1") (pinfunction "1_1") (pintype "passive"))
      (node (ref "C279") (pin "1") (pinfunction "1_1") (pintype "passive"))
      (node (ref "C280") (pin "1") (pinfunction "1_1") (pintype "passive"))
      (node (ref "C281") (pin "1") (pinfunction "1_1") (pintype "passive"))
      (node (ref "C284") (pin "1") (pinfunction "1_1") (pintype "passive"))
      (node (ref "C285") (pin "1") (pinfunction "1_1") (pintype "passive"))
      (node (ref "C286") (pin "1") (pinfunction "1_1") (pintype "passive"))
      (node (ref "C287") (pin "1") (pinfunction "1_1") (pintype "passive"))
      (node (ref "C288") (pin "1") (pinfunction "1_1") (pintype "passive"))
      (node (ref "C289") (pin "1") (pinfunction "1_1") (pintype "passive"))
      (node (ref "C290") (pin "1") (pinfunction "1_1") (pintype "passive"))
      (node (ref "C291") (pin "1") (pinfunction "1_1") (pintype "passive"))
      (node (ref "C292") (pin "1") (pinfunction "1_1") (pintype "passive"))
      (node (ref "C293") (pin "1") (pinfunction "1_1") (pintype "passive"))
      (node (ref "C294") (pin "1") (pinfunction "1_1") (pintype "passive"))
      (node (ref "C295") (pin "1") (pinfunction "1_1") (pintype "passive"))
      (node (ref "C296") (pin "2") (pinfunction "2_2") (pintype "passive"))
      (node (ref "C297") (pin "2") (pinfunction "2_2") (pintype "passive"))
      (node (ref "C298") (pin "2") (pinfunction "2_2") (pintype "passive"))
      (node (ref "C299") (pin "2") (pinfunction "2_2") (pintype "passive"))
      (node (ref "J13") (pin "1") (pinfunction "GND1_1") (pintype "passive"))
      (node (ref "J13") (pin "18") (pinfunction "GND3_18") (pintype "passive"))
      (node (ref "J13") (pin "33") (pinfunction "GND5_33") (pintype "passive"))
      (node (ref "J13") (pin "39") (pinfunction "GND4_39") (pintype "passive"))
      (node (ref "J13") (pin "45") (pinfunction "GND6_45") (pintype "passive"))
      (node (ref "J13") (pin "51") (pinfunction "GND7_51") (pintype "passive"))
      (node (ref "J13") (pin "57") (pinfunction "GND8_57") (pintype "passive"))
      (node (ref "J13") (pin "63") (pinfunction "GND9_63") (pintype "passive"))
      (node (ref "J13") (pin "69") (pinfunction "GND10_69") (pintype "passive"))
      (node (ref "J13") (pin "7") (pinfunction "GND2_7") (pintype "passive"))
      (node (ref "J13") (pin "75") (pinfunction "GND11_75") (pintype "passive"))
      (node (ref "J13") (pin "S1") (pinfunction "SHIELD_S1") (pintype "passive"))
      (node (ref "J13") (pin "S2") (pinfunction "SHIELD_S2") (pintype "passive"))
      (node (ref "R156") (pin "1") (pinfunction "1_1") (pintype "passive"))
      (node (ref "R157") (pin "1") (pinfunction "1_1") (pintype "passive"))
      (node (ref "R163") (pin "1") (pinfunction "1_1") (pintype "passive"))
      (node (ref "R164") (pin "1") (pinfunction "1_1") (pintype "passive"))
      (node (ref "R165") (pin "1") (pinfunction "1_1") (pintype "passive"))
      (node (ref "R170") (pin "2") (pinfunction "2_2") (pintype "passive"))
      (node (ref "U10") (pin "6") (pinfunction "NC_6") (pintype "passive"))
      (node (ref "U10") (pin "9") (pinfunction "NC_9") (pintype "passive"))
      (node (ref "U11") (pin "11") (pinfunction "VSS_11") (pintype "power_in"))
      (node (ref "U11") (pin "13") (pinfunction "A1_P_13") (pintype "passive"))
      (node (ref "U11") (pin "14") (pinfunction "A1_N_14") (pintype "passive"))
      (node (ref "U11") (pin "17") (pinfunction "EPAD_17") (pintype "power_in"))
      (node (ref "U11") (pin "3") (pinfunction "XSD_3") (pintype "passive"))
      (node (ref "U12") (pin "10") (pinfunction "GND_1_10") (pintype "passive"))
      (node (ref "U12") (pin "15") (pinfunction "GNDA_15") (pintype "passive"))
      (node (ref "U12") (pin "21") (pinfunction "GND_2_21") (pintype "passive"))
      (node (ref "U12") (pin "24") (pinfunction "GNDXTAL_24") (pintype "passive"))
      (node (ref "U12") (pin "25") (pinfunction "GND_3_25") (pintype "passive"))
      (node (ref "U12") (pin "5") (pinfunction "GNDREF_5") (pintype "passive"))
      (node (ref "U12") (pin "6") (pinfunction "GNDDIG_6") (pintype "passive"))
      (node (ref "U13") (pin "11") (pinfunction "VSS_11") (pintype "power_in"))
      (node (ref "U13") (pin "13") (pinfunction "A1_P_13") (pintype "passive"))
      (node (ref "U13") (pin "14") (pinfunction "A1_N_14") (pintype "passive"))
      (node (ref "U13") (pin "17") (pinfunction "EPAD_17") (pintype "power_in"))
      (node (ref "U13") (pin "3") (pinfunction "XSD_3") (pintype "passive"))
      (node (ref "U14") (pin "1") (pinfunction "NC_1") (pintype "passive"))
      (node (ref "U14") (pin "3") (pinfunction "GND_3") (pintype "power_in"))
      (node (ref "U15") (pin "3") (pinfunction "GND_3") (pintype "passive"))
      (node (ref "U16") (pin "2") (pinfunction "GND_2") (pintype "passive"))
      (node (ref "Y4") (pin "2") (pinfunction "GND_2") (pintype "passive"))
      (node (ref "Y5") (pin "2") (pinfunction "2_2") (pintype "passive"))
      (node (ref "Y5") (pin "4") (pinfunction "4_4") (pintype "passive"))
    )
    (net (code "76") (name "Net-(D10-A)") (class "Default")
      (node (ref "D10") (pin "2") (pinfunction "A_2") (pintype "passive"))
      (node (ref "R143") (pin "1") (pinfunction "1_1") (pintype "passive"))
    )
    (net (code "77") (name "Net-(D11-A)") (class "Default")
      (node (ref "D11") (pin "2") (pinfunction "A_2") (pintype "passive"))
      (node (ref "R144") (pin "1") (pinfunction "1_1") (pintype "passive"))
    )
    (net (code "78") (name "Net-(J13-CLKREQ0)") (class "Default")
      (node (ref "J13") (pin "53") (pinfunction "CLKREQ0_53") (pintype "passive"))
      (node (ref "R155") (pin "2") (pinfunction "2_2") (pintype "passive"))
    )
    (net (code "79") (name "Net-(J13-PERST0)") (class "Default")
      (node (ref "J13") (pin "52") (pinfunction "PERST0_52") (pintype "passive"))
      (node (ref "R153") (pin "2") (pinfunction "2_2") (pintype "passive"))
    )
    (net (code "80") (name "Net-(U10-OE)") (class "Default")
      (node (ref "R145") (pin "1") (pinfunction "1_1") (pintype "passive"))
      (node (ref "U10") (pin "8") (pinfunction "OE_8") (pintype "passive"))
    )
    (net (code "81") (name "Net-(U12-DIF0#)") (class "Default")
      (node (ref "R162") (pin "1") (pinfunction "1_1") (pintype "passive"))
      (node (ref "U12") (pin "14") (pinfunction "DIF0#_14") (pintype "passive"))
    )
    (net (code "82") (name "Net-(U12-DIF0)") (class "Default")
      (node (ref "R161") (pin "1") (pinfunction "1_1") (pintype "passive"))
      (node (ref "U12") (pin "13") (pinfunction "DIF0_13") (pintype "passive"))
    )
    (net (code "83") (name "Net-(U12-DIF1#)") (class "Default")
      (node (ref "R159") (pin "1") (pinfunction "1_1") (pintype "passive"))
      (node (ref "U12") (pin "18") (pinfunction "DIF1#_18") (pintype "passive"))
    )
    (net (code "84") (name "Net-(U12-DIF1)") (class "Default")
      (node (ref "R158") (pin "1") (pinfunction "1_1") (pintype "passive"))
      (node (ref "U12") (pin "17") (pinfunction "DIF1_17") (pintype "passive"))
    )
    (net (code "85") (name "Net-(U12-OE0#)") (class "Default")
      (node (ref "R164") (pin "2") (pinfunction "2_2") (pintype "passive"))
      (node (ref "U12") (pin "12") (pinfunction "OE0#_12") (pintype "passive"))
    )
    (net (code "86") (name "Net-(U12-OE1#)") (class "Default")
      (node (ref "R165") (pin "2") (pinfunction "2_2") (pintype "passive"))
      (node (ref "U12") (pin "19") (pinfunction "OE1#_19") (pintype "passive"))
    )
    (net (code "87") (name "Net-(U12-SADR{slash}REF1.8)") (class "Default")
      (node (ref "TP46") (pin "1") (pinfunction "1_1") (pintype "passive"))
      (node (ref "U12") (pin "4") (pinfunction "SADR/REF1.8_4") (pintype "passive"))
    )
    (net (code "88") (name "Net-(U12-VDD1.8_1)") (class "Default")
      (node (ref "C289") (pin "2") (pinfunction "2_2") (pintype "passive"))
      (node (ref "C290") (pin "2") (pinfunction "2_2") (pintype "passive"))
      (node (ref "C291") (pin "2") (pinfunction "2_2") (pintype "passive"))
      (node (ref "FB5") (pin "2") (pinfunction "2_2") (pintype "passive"))
      (node (ref "U12") (pin "11") (pinfunction "VDD1.8_1_11") (pintype "passive"))
      (node (ref "U12") (pin "20") (pinfunction "VDD1.8_2_20") (pintype "passive"))
    )
    (net (code "89") (name "Net-(U12-VDDA1.8)") (class "Default")
      (node (ref "C286") (pin "2") (pinfunction "2_2") (pintype "passive"))
      (node (ref "C287") (pin "2") (pinfunction "2_2") (pintype "passive"))
      (node (ref "C288") (pin "2") (pinfunction "2_2") (pintype "passive"))
      (node (ref "FB4") (pin "1") (pinfunction "1_1") (pintype "passive"))
      (node (ref "U12") (pin "16") (pinfunction "VDDA1.8_16") (pintype "passive"))
      (node (ref "U12") (pin "3") (pinfunction "VDDXTAL1.8_3") (pintype "passive"))
    )
    (net (code "90") (name "Net-(U16-DIR)") (class "Default")
      (node (ref "R170") (pin "1") (pinfunction "1_1") (pintype "passive"))
      (node (ref "U16") (pin "5") (pinfunction "DIR_5") (pintype "passive"))
    )
    (net (code "91") (name "unconnected-(J13-ALERT-Pad62)") (class "Default")
      (node (ref "J13") (pin "62") (pinfunction "ALERT_62") (pintype "passive+no_connect"))
    )
    (net (code "92") (name "unconnected-(J13-CLKREQ1-Pad68)") (class "Default")
      (node (ref "J13") (pin "68") (pinfunction "CLKREQ1_68") (pintype "passive+no_connect"))
    )
    (net (code "93") (name "unconnected-(J13-COEX1-Pad48)") (class "Default")
      (node (ref "J13") (pin "48") (pinfunction "COEX1_48") (pintype "passive+no_connect"))
    )
    (net (code "94") (name "unconnected-(J13-COEX2-Pad46)") (class "Default")
      (node (ref "J13") (pin "46") (pinfunction "COEX2_46") (pintype "passive+no_connect"))
    )
    (net (code "95") (name "unconnected-(J13-COEX3-Pad44)") (class "Default")
      (node (ref "J13") (pin "44") (pinfunction "COEX3_44") (pintype "passive+no_connect"))
    )
    (net (code "96") (name "unconnected-(J13-PERST1-Pad66)") (class "Default")
      (node (ref "J13") (pin "66") (pinfunction "PERST1_66") (pintype "passive+no_connect"))
    )
    (net (code "97") (name "unconnected-(J13-PER_N1-Pad67)") (class "Default")
      (node (ref "J13") (pin "67") (pinfunction "PER_N1_67") (pintype "passive+no_connect"))
    )
    (net (code "98") (name "unconnected-(J13-PER_P1-Pad65)") (class "Default")
      (node (ref "J13") (pin "65") (pinfunction "PER_P1_65") (pintype "passive+no_connect"))
    )
    (net (code "99") (name "unconnected-(J13-PET_N1-Pad61)") (class "Default")
      (node (ref "J13") (pin "61") (pinfunction "PET_N1_61") (pintype "passive+no_connect"))
    )
    (net (code "100") (name "unconnected-(J13-PET_P1-Pad59)") (class "Default")
      (node (ref "J13") (pin "59") (pinfunction "PET_P1_59") (pintype "passive+no_connect"))
    )
    (net (code "101") (name "unconnected-(J13-PEWAKE1-Pad70)") (class "Default")
      (node (ref "J13") (pin "70") (pinfunction "PEWAKE1_70") (pintype "passive+no_connect"))
    )
    (net (code "102") (name "unconnected-(J13-REFCLK_N1-Pad73)") (class "Default")
      (node (ref "J13") (pin "73") (pinfunction "REFCLK_N1_73") (pintype "passive+no_connect"))
    )
    (net (code "103") (name "unconnected-(J13-REFCLK_P1-Pad71)") (class "Default")
      (node (ref "J13") (pin "71") (pinfunction "REFCLK_P1_71") (pintype "passive+no_connect"))
    )
    (net (code "104") (name "unconnected-(J13-RESERVED-Pad64)") (class "Default")
      (node (ref "J13") (pin "64") (pinfunction "RESERVED_64") (pintype "passive+no_connect"))
    )
    (net (code "105") (name "unconnected-(J13-SDIO_CLK-Pad9)") (class "Default")
      (node (ref "J13") (pin "9") (pinfunction "SDIO_CLK_9") (pintype "passive+no_connect"))
    )
    (net (code "106") (name "unconnected-(J13-SDIO_CMD-Pad11)") (class "Default")
      (node (ref "J13") (pin "11") (pinfunction "SDIO_CMD_11") (pintype "passive+no_connect"))
    )
    (net (code "107") (name "unconnected-(J13-SDIO_DATA0-Pad13)") (class "Default")
      (node (ref "J13") (pin "13") (pinfunction "SDIO_DATA0_13") (pintype "passive+no_connect"))
    )
    (net (code "108") (name "unconnected-(J13-SDIO_DATA1-Pad15)") (class "Default")
      (node (ref "J13") (pin "15") (pinfunction "SDIO_DATA1_15") (pintype "passive+no_connect"))
    )
    (net (code "109") (name "unconnected-(J13-SDIO_DATA2-Pad17)") (class "Default")
      (node (ref "J13") (pin "17") (pinfunction "SDIO_DATA2_17") (pintype "passive+no_connect"))
    )
    (net (code "110") (name "unconnected-(J13-SDIO_DATA3-Pad19)") (class "Default")
      (node (ref "J13") (pin "19") (pinfunction "SDIO_DATA3_19") (pintype "passive+no_connect"))
    )
    (net (code "111") (name "unconnected-(J13-VEN_DEF1-Pad38)") (class "Default")
      (node (ref "J13") (pin "38") (pinfunction "VEN_DEF1_38") (pintype "passive+no_connect"))
    )
    (net (code "112") (name "unconnected-(J13-VEN_DEF2-Pad40)") (class "Default")
      (node (ref "J13") (pin "40") (pinfunction "VEN_DEF2_40") (pintype "passive+no_connect"))
    )
    (net (code "113") (name "unconnected-(J13-VEN_DEF3-Pad42)") (class "Default")
      (node (ref "J13") (pin "42") (pinfunction "VEN_DEF3_42") (pintype "passive+no_connect"))
    )
    (net (code "114") (name "unconnected-(U10-EP-Pad15)") (class "Default")
      (node (ref "U10") (pin "15") (pinfunction "EP_15") (pintype "passive+no_connect"))
    )
    (net (code "115") (name "unconnected-(U10-GND-Pad7)") (class "Default")
      (node (ref "U10") (pin "7") (pinfunction "GND_7") (pintype "power_in+no_connect"))
    )
    (net (code "116") (name "unconnected-(U11-B1_N-Pad1)") (class "Default")
      (node (ref "U11") (pin "1") (pinfunction "B1_N_1") (pintype "passive+no_connect"))
    )
    (net (code "117") (name "unconnected-(U11-B1_P-Pad2)") (class "Default")
      (node (ref "U11") (pin "2") (pinfunction "B1_P_2") (pintype "passive+no_connect"))
    )
    (net (code "118") (name "unconnected-(U11-C1_N-Pad16)") (class "Default")
      (node (ref "U11") (pin "16") (pinfunction "C1_N_16") (pintype "passive+no_connect"))
    )
    (net (code "119") (name "unconnected-(U11-C1_P-Pad15)") (class "Default")
      (node (ref "U11") (pin "15") (pinfunction "C1_P_15") (pintype "passive+no_connect"))
    )
    (net (code "120") (name "unconnected-(U13-B1_N-Pad1)") (class "Default")
      (node (ref "U13") (pin "1") (pinfunction "B1_N_1") (pintype "passive+no_connect"))
    )
    (net (code "121") (name "unconnected-(U13-B1_P-Pad2)") (class "Default")
      (node (ref "U13") (pin "2") (pinfunction "B1_P_2") (pintype "passive+no_connect"))
    )
    (net (code "122") (name "unconnected-(U13-C1_N-Pad16)") (class "Default")
      (node (ref "U13") (pin "16") (pinfunction "C1_N_16") (pintype "passive+no_connect"))
    )
    (net (code "123") (name "unconnected-(U13-C1_P-Pad15)") (class "Default")
      (node (ref "U13") (pin "15") (pinfunction "C1_P_15") (pintype "passive+no_connect"))
    )
  )
)
